# 1port.net
KiCad netlist of a schematic drawn in EAGLE
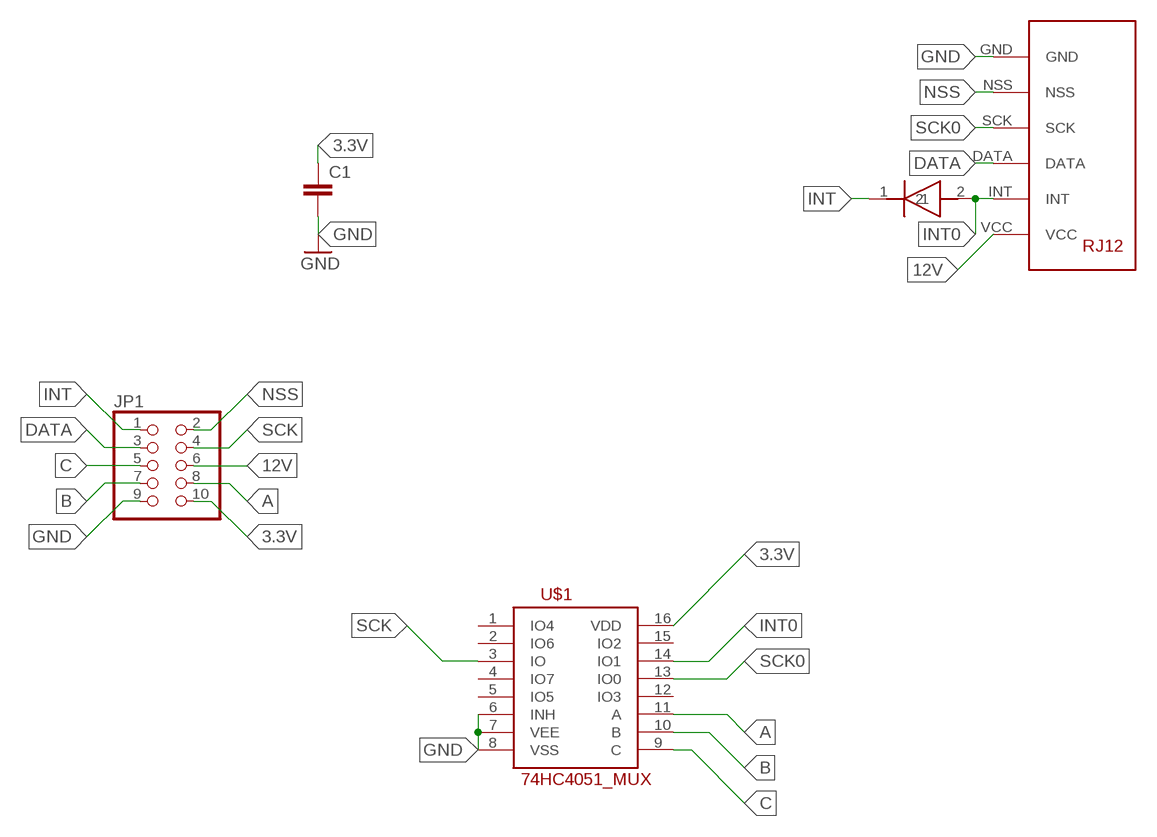
[diagram p0: schematic, sheet 1]

(export (version "E")
  (design (tool "Eeschema 10.0.6"))
  (components
    (comp (ref "C1")
      (value "C-EUC1206")
      (footprint "eagle-import:C1206")
      (libsource (lib "eagle-import") (part "C-EUC1206"))
    )
    (comp (ref "JP1")
      (value "PINHD-2X5")
      (footprint "eagle-import:2X05")
      (libsource (lib "eagle-import") (part "PINHD-2X5"))
    )
    (comp (ref "U$1")
      (value "74HC4051_MUX")
      (footprint "eagle-import:SO16")
      (libsource (lib "eagle-import") (part "74HC4051_MUX"))
    )
    (comp (ref "U$4")
      (value "RJ12SMD")
      (footprint "eagle-import:RJ12_SMD")
      (libsource (lib "eagle-import") (part "RJ12SMD"))
    )
    (comp (ref "U$9")
      (value "DIODE")
      (footprint "eagle-import:DIL_DIODE_SMD")
      (libsource (lib "eagle-import") (part "DIODE"))
    )
  )
  (nets
    (net (code "1") (name "3.3V") (class "Default")
      (node (ref "C1") (pin "1") (pinfunction "1_1") (pintype "passive"))
      (node (ref "JP1") (pin "10") (pinfunction "10_10") (pintype "passive"))
      (node (ref "U$1") (pin "16") (pinfunction "VDD_16") (pintype "bidirectional"))
    )
    (net (code "2") (name "12V") (class "Default")
      (node (ref "JP1") (pin "6") (pinfunction "6_6") (pintype "passive"))
      (node (ref "U$4") (pin "VCC") (pinfunction "VCC_VCC") (pintype "bidirectional"))
    )
    (net (code "3") (name "A") (class "Default")
      (node (ref "JP1") (pin "8") (pinfunction "8_8") (pintype "passive"))
      (node (ref "U$1") (pin "11") (pinfunction "A_11") (pintype "bidirectional"))
    )
    (net (code "4") (name "B") (class "Default")
      (node (ref "JP1") (pin "7") (pinfunction "7_7") (pintype "passive"))
      (node (ref "U$1") (pin "10") (pinfunction "B_10") (pintype "bidirectional"))
    )
    (net (code "5") (name "C") (class "Default")
      (node (ref "JP1") (pin "5") (pinfunction "5_5") (pintype "passive"))
      (node (ref "U$1") (pin "9") (pinfunction "C_9") (pintype "bidirectional"))
    )
    (net (code "6") (name "DATA") (class "Default")
      (node (ref "JP1") (pin "3") (pinfunction "3_3") (pintype "passive"))
      (node (ref "U$4") (pin "DATA") (pinfunction "DATA_DATA") (pintype "bidirectional"))
    )
    (net (code "7") (name "GND") (class "Default")
      (node (ref "C1") (pin "2") (pinfunction "2_2") (pintype "passive"))
      (node (ref "JP1") (pin "9") (pinfunction "9_9") (pintype "passive"))
      (node (ref "U$1") (pin "6") (pinfunction "INH_6") (pintype "bidirectional"))
      (node (ref "U$1") (pin "7") (pinfunction "VEE_7") (pintype "bidirectional"))
      (node (ref "U$1") (pin "8") (pinfunction "VSS_8") (pintype "bidirectional"))
      (node (ref "U$4") (pin "GND") (pinfunction "GND_GND") (pintype "bidirectional"))
    )
    (net (code "8") (name "INT") (class "Default")
      (node (ref "JP1") (pin "1") (pinfunction "1_1") (pintype "passive"))
      (node (ref "U$9") (pin "1") (pinfunction "1_1") (pintype "bidirectional"))
    )
    (net (code "9") (name "INT0") (class "Default")
      (node (ref "U$1") (pin "14") (pinfunction "IO1_14") (pintype "bidirectional"))
      (node (ref "U$4") (pin "INT") (pinfunction "INT_INT") (pintype "bidirectional"))
      (node (ref "U$9") (pin "2") (pinfunction "2_2") (pintype "bidirectional"))
    )
    (net (code "10") (name "NSS") (class "Default")
      (node (ref "JP1") (pin "2") (pinfunction "2_2") (pintype "passive"))
      (node (ref "U$4") (pin "NSS") (pinfunction "NSS_NSS") (pintype "bidirectional"))
    )
    (net (code "11") (name "SCK") (class "Default")
      (node (ref "JP1") (pin "4") (pinfunction "4_4") (pintype "passive"))
      (node (ref "U$1") (pin "3") (pinfunction "IO_3") (pintype "bidirectional"))
    )
    (net (code "12") (name "SCK0") (class "Default")
      (node (ref "U$1") (pin "13") (pinfunction "IO0_13") (pintype "bidirectional"))
      (node (ref "U$4") (pin "SCK") (pinfunction "SCK_SCK") (pintype "bidirectional"))
    )
    (net (code "13") (name "unconnected-(U$1-IO2-Pad15)") (class "Default")
      (node (ref "U$1") (pin "15") (pinfunction "IO2_15") (pintype "bidirectional"))
    )
    (net (code "14") (name "unconnected-(U$1-IO3-Pad12)") (class "Default")
      (node (ref "U$1") (pin "12") (pinfunction "IO3_12") (pintype "bidirectional"))
    )
    (net (code "15") (name "unconnected-(U$1-IO4-Pad1)") (class "Default")
      (node (ref "U$1") (pin "1") (pinfunction "IO4_1") (pintype "bidirectional"))
    )
    (net (code "16") (name "unconnected-(U$1-IO5-Pad5)") (class "Default")
      (node (ref "U$1") (pin "5") (pinfunction "IO5_5") (pintype "bidirectional"))
    )
    (net (code "17") (name "unconnected-(U$1-IO6-Pad2)") (class "Default")
      (node (ref "U$1") (pin "2") (pinfunction "IO6_2") (pintype "bidirectional"))
    )
    (net (code "18") (name "unconnected-(U$1-IO7-Pad4)") (class "Default")
      (node (ref "U$1") (pin "4") (pinfunction "IO7_4") (pintype "bidirectional"))
    )
  )
)
